# Monitoring.net
KiCad netlist of a schematic drawn in Altium Designer
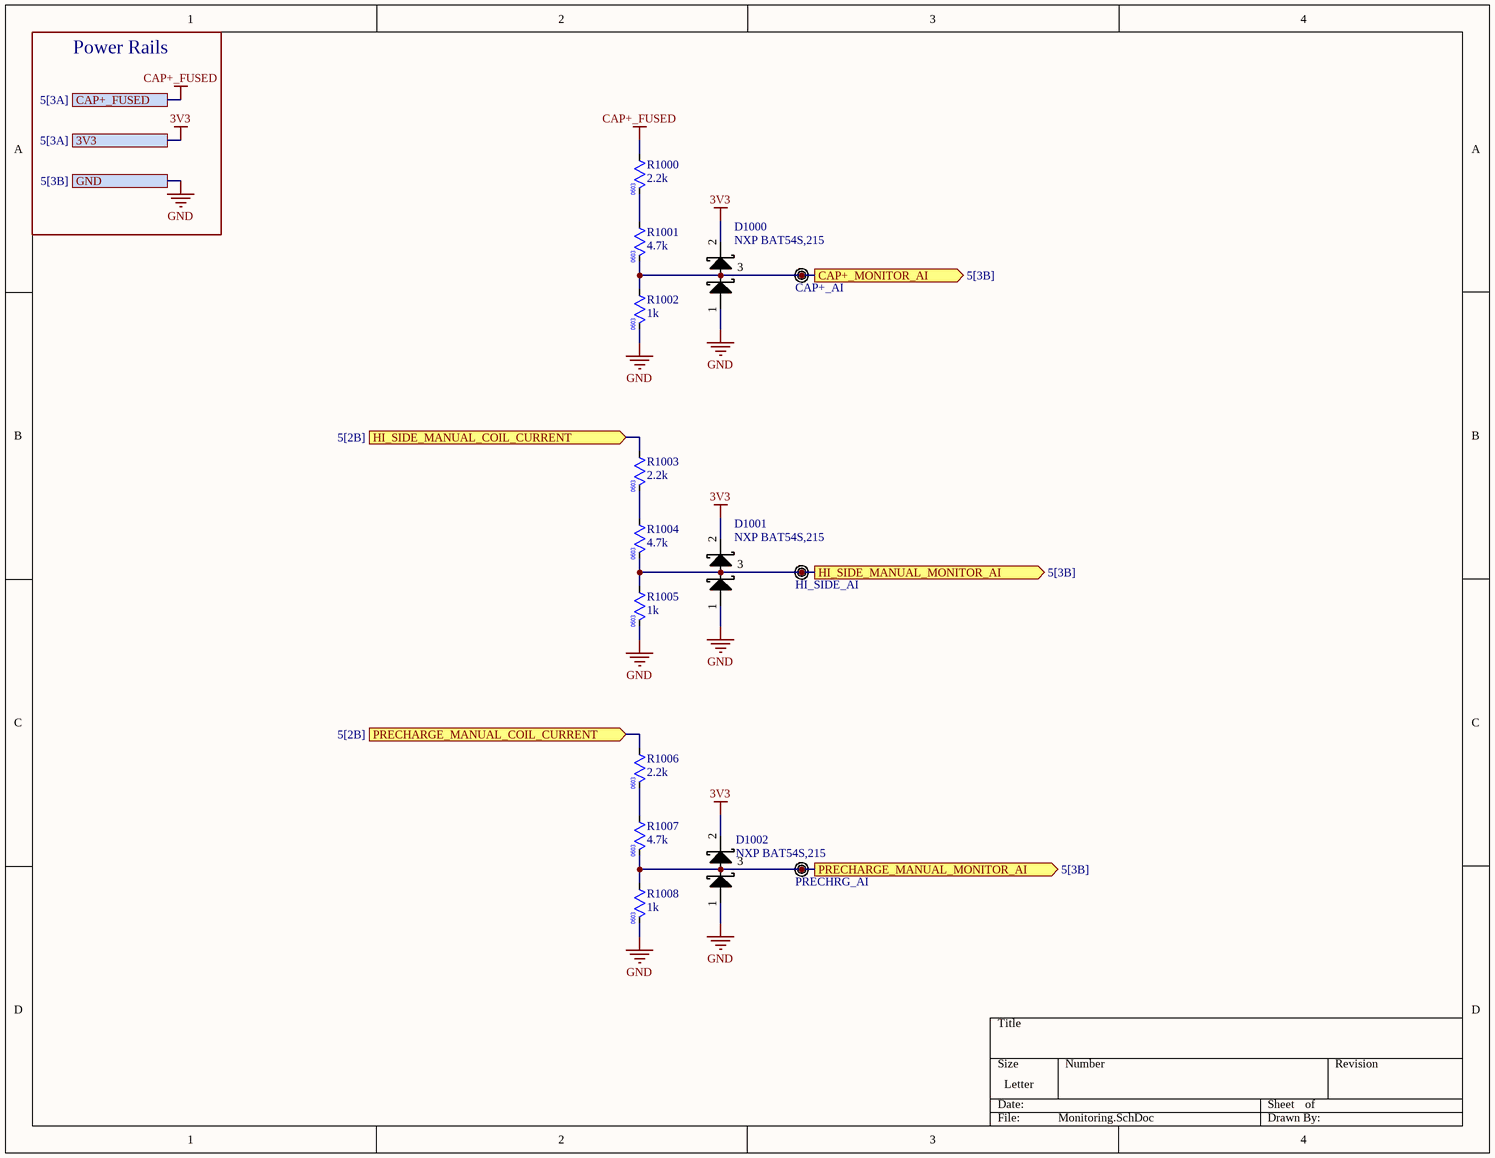
[diagram p0: Monitoring.SchDoc]

(export (version "E")
  (design (tool "Eeschema 10.0.6"))
  (components
    (comp (ref "D1000")
      (value "NXP BAT54S,215")
      (footprint "NXP BAT54S,215")
      (description "DIODE ARRAY SCHOTTKY 30V SOT23 / Diode Schottky 0.2A Automotive 3-Pin TO-236AB T/R")
      (libsource (lib "UBC Formula Electric") (part "NXP BAT54S,215"))
    )
    (comp (ref "D1001")
      (value "NXP BAT54S,215")
      (footprint "NXP BAT54S,215")
      (description "DIODE ARRAY SCHOTTKY 30V SOT23 / Diode Schottky 0.2A Automotive 3-Pin TO-236AB T/R")
      (libsource (lib "UBC Formula Electric") (part "NXP BAT54S,215"))
    )
    (comp (ref "D1002")
      (value "NXP BAT54S,215")
      (footprint "NXP BAT54S,215")
      (description "DIODE ARRAY SCHOTTKY 30V SOT23 / Diode Schottky 0.2A Automotive 3-Pin TO-236AB T/R")
      (libsource (lib "UBC Formula Electric") (part "NXP BAT54S,215"))
    )
    (comp (ref "R1000")
      (value "2.2k")
      (footprint "0603 Resistor Footprint")
      (description "RES SMD 2.2K OHM 1% 1/4W 0603")
      (fields
        (field (name "DIGIKEY PART NUMBER") "541-10449-1-ND")
        (field (name "MANUFACTURER PART NUMBER") "RCS06032K20FKEA")
      )
      (libsource (lib "UBC Formula Electric") (part "RES-2"))
    )
    (comp (ref "R1001")
      (value "4.7k")
      (footprint "0603 Resistor Footprint")
      (description "RES SMD 4.7K OHM 1% 1/3W 0603")
      (fields (field (name "TOLERANCE") "1%") (field (name "POWER") "250mW"))
      (libsource (lib "UBC Formula Electric") (part "RES-2"))
    )
    (comp (ref "R1002")
      (value "1k")
      (footprint "0603 Resistor Footprint")
      (description "RES SMD 1K OHM 1% 1/3W 0603")
      (fields (field (name "TOLERANCE") "1%") (field (name "POWER") "250mW"))
      (libsource (lib "UBC Formula Electric") (part "RES-2"))
    )
    (comp (ref "R1003")
      (value "2.2k")
      (footprint "0603 Resistor Footprint")
      (description "RES SMD 2.2K OHM 1% 1/4W 0603")
      (fields
        (field (name "DIGIKEY PART NUMBER") "541-10449-1-ND")
        (field (name "MANUFACTURER PART NUMBER") "RCS06032K20FKEA")
      )
      (libsource (lib "UBC Formula Electric") (part "RES-2"))
    )
    (comp (ref "R1004")
      (value "4.7k")
      (footprint "0603 Resistor Footprint")
      (description "RES SMD 4.7K OHM 1% 1/3W 0603")
      (fields (field (name "TOLERANCE") "1%") (field (name "POWER") "250mW"))
      (libsource (lib "UBC Formula Electric") (part "RES-2"))
    )
    (comp (ref "R1005")
      (value "1k")
      (footprint "0603 Resistor Footprint")
      (description "RES SMD 1K OHM 1% 1/3W 0603")
      (fields (field (name "TOLERANCE") "1%") (field (name "POWER") "250mW"))
      (libsource (lib "UBC Formula Electric") (part "RES-2"))
    )
    (comp (ref "R1006")
      (value "2.2k")
      (footprint "0603 Resistor Footprint")
      (description "RES SMD 2.2K OHM 1% 1/4W 0603")
      (fields
        (field (name "DIGIKEY PART NUMBER") "541-10449-1-ND")
        (field (name "MANUFACTURER PART NUMBER") "RCS06032K20FKEA")
      )
      (libsource (lib "UBC Formula Electric") (part "RES-2"))
    )
    (comp (ref "R1007")
      (value "4.7k")
      (footprint "0603 Resistor Footprint")
      (description "RES SMD 4.7K OHM 1% 1/3W 0603")
      (fields (field (name "TOLERANCE") "1%") (field (name "POWER") "250mW"))
      (libsource (lib "UBC Formula Electric") (part "RES-2"))
    )
    (comp (ref "R1008")
      (value "1k")
      (footprint "0603 Resistor Footprint")
      (description "RES SMD 1K OHM 1% 1/3W 0603")
      (fields (field (name "TOLERANCE") "1%") (field (name "POWER") "250mW"))
      (libsource (lib "UBC Formula Electric") (part "RES-2"))
    )
    (comp (ref "TP1000")
      (value "CAP+_AI")
      (footprint "TESTPOINT")
      (fields (field (name "SOURCE") "UBC Formula Electric.SchLib"))
      (libsource (lib "UBC Formula Electric") (part "Thru-Hole Test Point"))
    )
    (comp (ref "TP1001")
      (value "HI_SIDE_AI")
      (footprint "TESTPOINT")
      (fields (field (name "SOURCE") "UBC Formula Electric.SchLib"))
      (libsource (lib "UBC Formula Electric") (part "Thru-Hole Test Point"))
    )
    (comp (ref "TP1002")
      (value "PRECHRG_AI")
      (footprint "TESTPOINT")
      (fields (field (name "SOURCE") "UBC Formula Electric.SchLib"))
      (libsource (lib "UBC Formula Electric") (part "Thru-Hole Test Point"))
    )
  )
  (nets
    (net (code "1") (name "/CAP+_MONITOR_AI") (class "Default")
      (node (ref "D1000") (pin "3") (pinfunction "3_3") (pintype "passive"))
      (node (ref "R1001") (pin "2") (pinfunction "2_2") (pintype "passive"))
      (node (ref "R1002") (pin "1") (pinfunction "1_1") (pintype "passive"))
      (node (ref "TP1000") (pin "1") (pinfunction "TP_1") (pintype "passive"))
    )
    (net (code "2") (name "/HI_SIDE_MANUAL_COIL_CURRENT") (class "Default")
      (node (ref "R1003") (pin "1") (pinfunction "1_1") (pintype "passive"))
    )
    (net (code "3") (name "/HI_SIDE_MANUAL_MONITOR_AI") (class "Default")
      (node (ref "D1001") (pin "3") (pinfunction "3_3") (pintype "passive"))
      (node (ref "R1004") (pin "2") (pinfunction "2_2") (pintype "passive"))
      (node (ref "R1005") (pin "1") (pinfunction "1_1") (pintype "passive"))
      (node (ref "TP1001") (pin "1") (pinfunction "TP_1") (pintype "passive"))
    )
    (net (code "4") (name "/PRECHARGE_MANUAL_COIL_CURRENT") (class "Default")
      (node (ref "R1006") (pin "1") (pinfunction "1_1") (pintype "passive"))
    )
    (net (code "5") (name "/PRECHARGE_MANUAL_MONITOR_AI") (class "Default")
      (node (ref "D1002") (pin "3") (pinfunction "3_3") (pintype "passive"))
      (node (ref "R1007") (pin "2") (pinfunction "2_2") (pintype "passive"))
      (node (ref "R1008") (pin "1") (pinfunction "1_1") (pintype "passive"))
      (node (ref "TP1002") (pin "1") (pinfunction "TP_1") (pintype "passive"))
    )
    (net (code "6") (name "3V3") (class "Default")
      (node (ref "D1000") (pin "2") (pinfunction "2_2") (pintype "passive"))
      (node (ref "D1001") (pin "2") (pinfunction "2_2") (pintype "passive"))
      (node (ref "D1002") (pin "2") (pinfunction "2_2") (pintype "passive"))
    )
    (net (code "7") (name "CAP+_FUSED") (class "Default")
      (node (ref "R1000") (pin "1") (pinfunction "1_1") (pintype "passive"))
    )
    (net (code "8") (name "GND") (class "Default")
      (node (ref "D1000") (pin "1") (pinfunction "1_1") (pintype "passive"))
      (node (ref "D1001") (pin "1") (pinfunction "1_1") (pintype "passive"))
      (node (ref "D1002") (pin "1") (pinfunction "1_1") (pintype "passive"))
      (node (ref "R1002") (pin "2") (pinfunction "2_2") (pintype "passive"))
      (node (ref "R1005") (pin "2") (pinfunction "2_2") (pintype "passive"))
      (node (ref "R1008") (pin "2") (pinfunction "2_2") (pintype "passive"))
    )
    (net (code "9") (name "Net-(R1000-Pad2)") (class "Default")
      (node (ref "R1000") (pin "2") (pinfunction "2_2") (pintype "passive"))
      (node (ref "R1001") (pin "1") (pinfunction "1_1") (pintype "passive"))
    )
    (net (code "10") (name "Net-(R1003-Pad2)") (class "Default")
      (node (ref "R1003") (pin "2") (pinfunction "2_2") (pintype "passive"))
      (node (ref "R1004") (pin "1") (pinfunction "1_1") (pintype "passive"))
    )
    (net (code "11") (name "Net-(R1006-Pad2)") (class "Default")
      (node (ref "R1006") (pin "2") (pinfunction "2_2") (pintype "passive"))
      (node (ref "R1007") (pin "1") (pinfunction "1_1") (pintype "passive"))
    )
  )
)
